# Sheet6.net
KiCad netlist of a schematic drawn in Altium Designer
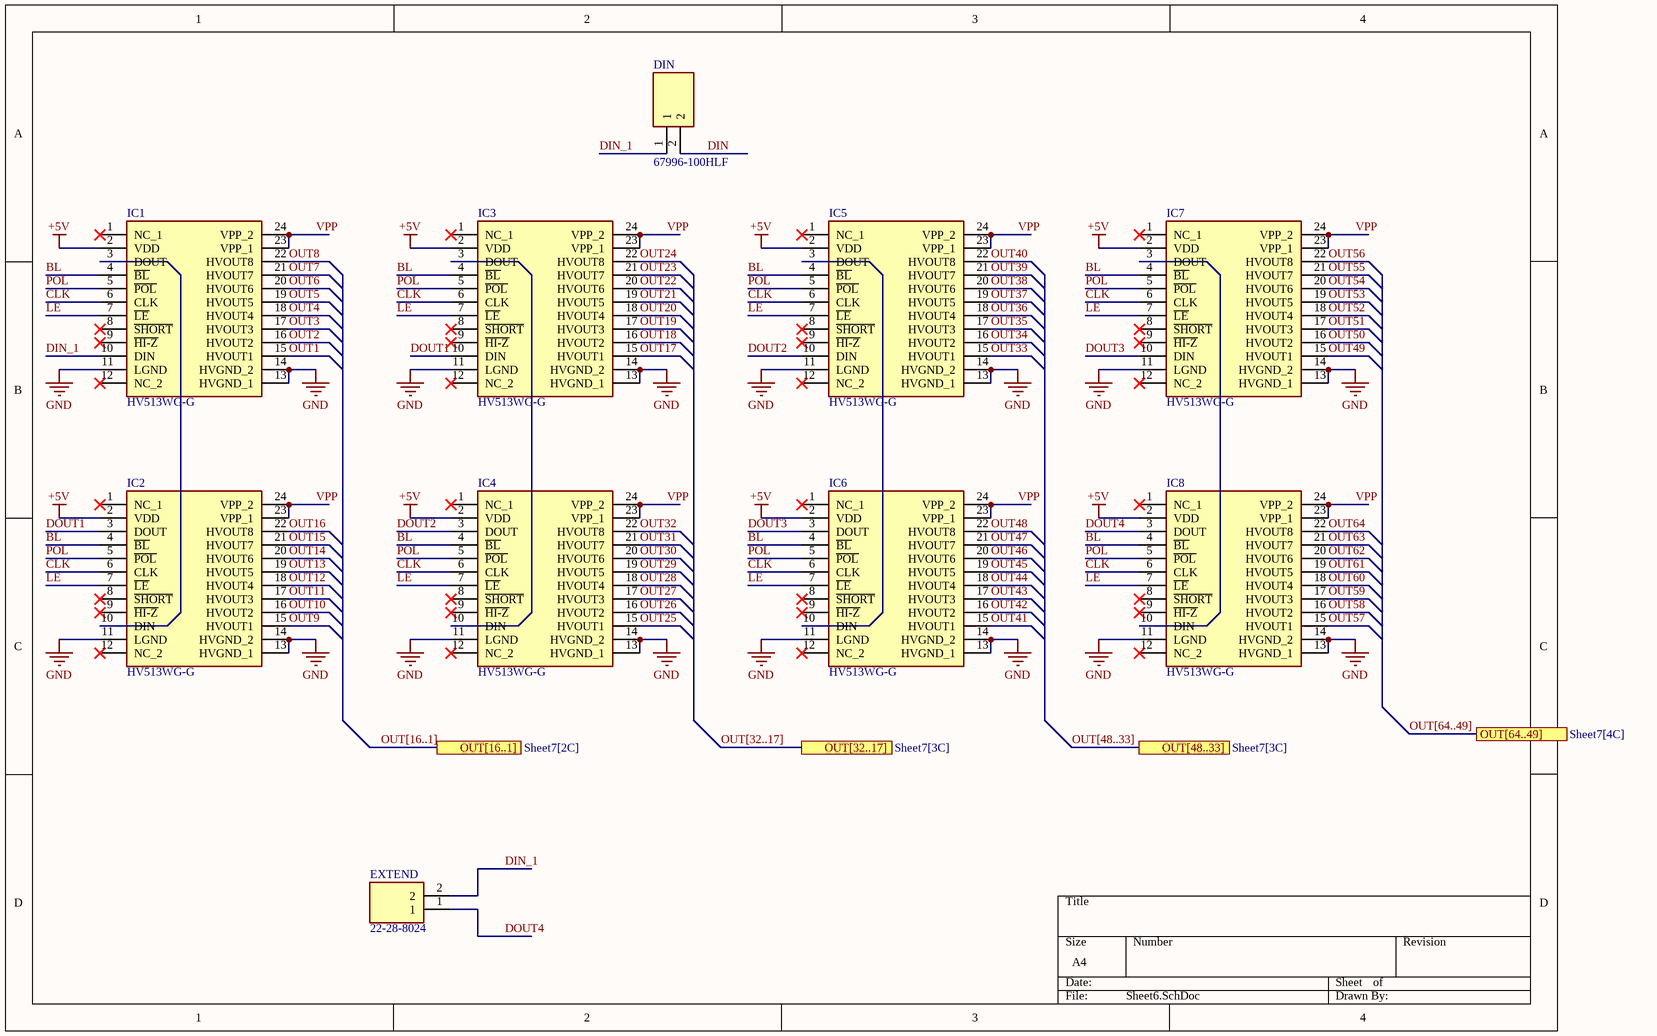
[diagram p0: Sheet6.SchDoc]

(export (version "E")
  (design (tool "Eeschema 10.0.6"))
  (components
    (comp (ref "DIN")
      (value "67996-100HLF")
      (footprint "HDRV2W67P254_2X1_254X483X858P")
      (libsource (lib "67996-100HLF") (part "67996-100HLF"))
    )
    (comp (ref "EXTEND")
      (value "22-28-8024")
      (footprint "SamacSys:HDRRA2W66P0X254_1X2_508X229X274P")
      (description "Connector")
      (libsource (lib "*") (part "22-28-8024"))
    )
    (comp (ref "IC1")
      (value "HV513WG-G")
      (footprint "SamacSys:SOIC127P1030X265-24N")
      (description "Integrated Circuit")
      (fields (field (name "MOUSER PART NUMBER") "689-HV513WG-G"))
      (libsource (lib "*") (part "HV513WG-G"))
    )
    (comp (ref "IC2")
      (value "HV513WG-G")
      (footprint "SamacSys:SOIC127P1030X265-24N")
      (description "Integrated Circuit")
      (fields (field (name "MOUSER PART NUMBER") "689-HV513WG-G"))
      (libsource (lib "*") (part "HV513WG-G"))
    )
    (comp (ref "IC3")
      (value "HV513WG-G")
      (footprint "SamacSys:SOIC127P1030X265-24N")
      (description "Integrated Circuit")
      (fields (field (name "MOUSER PART NUMBER") "689-HV513WG-G"))
      (libsource (lib "*") (part "HV513WG-G"))
    )
    (comp (ref "IC4")
      (value "HV513WG-G")
      (footprint "SamacSys:SOIC127P1030X265-24N")
      (description "Integrated Circuit")
      (fields (field (name "MOUSER PART NUMBER") "689-HV513WG-G"))
      (libsource (lib "*") (part "HV513WG-G"))
    )
    (comp (ref "IC5")
      (value "HV513WG-G")
      (footprint "SamacSys:SOIC127P1030X265-24N")
      (description "Integrated Circuit")
      (fields (field (name "MOUSER PART NUMBER") "689-HV513WG-G"))
      (libsource (lib "*") (part "HV513WG-G"))
    )
    (comp (ref "IC6")
      (value "HV513WG-G")
      (footprint "SamacSys:SOIC127P1030X265-24N")
      (description "Integrated Circuit")
      (fields (field (name "MOUSER PART NUMBER") "689-HV513WG-G"))
      (libsource (lib "*") (part "HV513WG-G"))
    )
    (comp (ref "IC7")
      (value "HV513WG-G")
      (footprint "SamacSys:SOIC127P1030X265-24N")
      (description "Integrated Circuit")
      (fields (field (name "MOUSER PART NUMBER") "689-HV513WG-G"))
      (libsource (lib "*") (part "HV513WG-G"))
    )
    (comp (ref "IC8")
      (value "HV513WG-G")
      (footprint "SamacSys:SOIC127P1030X265-24N")
      (description "Integrated Circuit")
      (fields (field (name "MOUSER PART NUMBER") "689-HV513WG-G"))
      (libsource (lib "*") (part "HV513WG-G"))
    )
  )
  (nets
    (net (code "1") (name "+5V") (class "Default")
      (node (ref "IC1") (pin "2") (pinfunction "VDD_2") (pintype "passive"))
      (node (ref "IC2") (pin "2") (pinfunction "VDD_2") (pintype "passive"))
      (node (ref "IC3") (pin "2") (pinfunction "VDD_2") (pintype "passive"))
      (node (ref "IC4") (pin "2") (pinfunction "VDD_2") (pintype "passive"))
      (node (ref "IC5") (pin "2") (pinfunction "VDD_2") (pintype "passive"))
      (node (ref "IC6") (pin "2") (pinfunction "VDD_2") (pintype "passive"))
      (node (ref "IC7") (pin "2") (pinfunction "VDD_2") (pintype "passive"))
      (node (ref "IC8") (pin "2") (pinfunction "VDD_2") (pintype "passive"))
    )
    (net (code "2") (name "/BL") (class "Default")
      (node (ref "IC1") (pin "4") (pinfunction "~{BL}_4") (pintype "passive"))
      (node (ref "IC2") (pin "4") (pinfunction "~{BL}_4") (pintype "passive"))
      (node (ref "IC3") (pin "4") (pinfunction "~{BL}_4") (pintype "passive"))
      (node (ref "IC4") (pin "4") (pinfunction "~{BL}_4") (pintype "passive"))
      (node (ref "IC5") (pin "4") (pinfunction "~{BL}_4") (pintype "passive"))
      (node (ref "IC6") (pin "4") (pinfunction "~{BL}_4") (pintype "passive"))
      (node (ref "IC7") (pin "4") (pinfunction "~{BL}_4") (pintype "passive"))
      (node (ref "IC8") (pin "4") (pinfunction "~{BL}_4") (pintype "passive"))
    )
    (net (code "3") (name "/CLK") (class "Default")
      (node (ref "IC1") (pin "6") (pinfunction "CLK_6") (pintype "passive"))
      (node (ref "IC2") (pin "6") (pinfunction "CLK_6") (pintype "passive"))
      (node (ref "IC3") (pin "6") (pinfunction "CLK_6") (pintype "passive"))
      (node (ref "IC4") (pin "6") (pinfunction "CLK_6") (pintype "passive"))
      (node (ref "IC5") (pin "6") (pinfunction "CLK_6") (pintype "passive"))
      (node (ref "IC6") (pin "6") (pinfunction "CLK_6") (pintype "passive"))
      (node (ref "IC7") (pin "6") (pinfunction "CLK_6") (pintype "passive"))
      (node (ref "IC8") (pin "6") (pinfunction "CLK_6") (pintype "passive"))
    )
    (net (code "4") (name "/DIN") (class "Default")
      (node (ref "DIN") (pin "2") (pinfunction "2_2") (pintype "passive"))
    )
    (net (code "5") (name "/DIN_1") (class "Default")
      (node (ref "DIN") (pin "1") (pinfunction "1_1") (pintype "passive"))
      (node (ref "EXTEND") (pin "2") (pinfunction "2_2") (pintype "passive"))
      (node (ref "IC1") (pin "10") (pinfunction "DIN_10") (pintype "passive"))
    )
    (net (code "6") (name "/DOUT1") (class "Default")
      (node (ref "IC2") (pin "3") (pinfunction "DOUT_3") (pintype "passive"))
      (node (ref "IC3") (pin "10") (pinfunction "DIN_10") (pintype "passive"))
    )
    (net (code "7") (name "/DOUT2") (class "Default")
      (node (ref "IC4") (pin "3") (pinfunction "DOUT_3") (pintype "passive"))
      (node (ref "IC5") (pin "10") (pinfunction "DIN_10") (pintype "passive"))
    )
    (net (code "8") (name "/DOUT3") (class "Default")
      (node (ref "IC6") (pin "3") (pinfunction "DOUT_3") (pintype "passive"))
      (node (ref "IC7") (pin "10") (pinfunction "DIN_10") (pintype "passive"))
    )
    (net (code "9") (name "/DOUT4") (class "Default")
      (node (ref "EXTEND") (pin "1") (pinfunction "1_1") (pintype "passive"))
      (node (ref "IC8") (pin "3") (pinfunction "DOUT_3") (pintype "passive"))
    )
    (net (code "10") (name "/LE") (class "Default")
      (node (ref "IC1") (pin "7") (pinfunction "~{LE}_7") (pintype "passive"))
      (node (ref "IC2") (pin "7") (pinfunction "~{LE}_7") (pintype "passive"))
      (node (ref "IC3") (pin "7") (pinfunction "~{LE}_7") (pintype "passive"))
      (node (ref "IC4") (pin "7") (pinfunction "~{LE}_7") (pintype "passive"))
      (node (ref "IC5") (pin "7") (pinfunction "~{LE}_7") (pintype "passive"))
      (node (ref "IC6") (pin "7") (pinfunction "~{LE}_7") (pintype "passive"))
      (node (ref "IC7") (pin "7") (pinfunction "~{LE}_7") (pintype "passive"))
      (node (ref "IC8") (pin "7") (pinfunction "~{LE}_7") (pintype "passive"))
    )
    (net (code "11") (name "/OUT1") (class "Default")
      (node (ref "IC1") (pin "15") (pinfunction "HVOUT1_15") (pintype "passive"))
    )
    (net (code "12") (name "/OUT2") (class "Default")
      (node (ref "IC1") (pin "16") (pinfunction "HVOUT2_16") (pintype "passive"))
    )
    (net (code "13") (name "/OUT3") (class "Default")
      (node (ref "IC1") (pin "17") (pinfunction "HVOUT3_17") (pintype "passive"))
    )
    (net (code "14") (name "/OUT4") (class "Default")
      (node (ref "IC1") (pin "18") (pinfunction "HVOUT4_18") (pintype "passive"))
    )
    (net (code "15") (name "/OUT5") (class "Default")
      (node (ref "IC1") (pin "19") (pinfunction "HVOUT5_19") (pintype "passive"))
    )
    (net (code "16") (name "/OUT6") (class "Default")
      (node (ref "IC1") (pin "20") (pinfunction "HVOUT6_20") (pintype "passive"))
    )
    (net (code "17") (name "/OUT7") (class "Default")
      (node (ref "IC1") (pin "21") (pinfunction "HVOUT7_21") (pintype "passive"))
    )
    (net (code "18") (name "/OUT8") (class "Default")
      (node (ref "IC1") (pin "22") (pinfunction "HVOUT8_22") (pintype "passive"))
    )
    (net (code "19") (name "/OUT9") (class "Default")
      (node (ref "IC2") (pin "15") (pinfunction "HVOUT1_15") (pintype "passive"))
    )
    (net (code "20") (name "/OUT10") (class "Default")
      (node (ref "IC2") (pin "16") (pinfunction "HVOUT2_16") (pintype "passive"))
    )
    (net (code "21") (name "/OUT11") (class "Default")
      (node (ref "IC2") (pin "17") (pinfunction "HVOUT3_17") (pintype "passive"))
    )
    (net (code "22") (name "/OUT12") (class "Default")
      (node (ref "IC2") (pin "18") (pinfunction "HVOUT4_18") (pintype "passive"))
    )
    (net (code "23") (name "/OUT13") (class "Default")
      (node (ref "IC2") (pin "19") (pinfunction "HVOUT5_19") (pintype "passive"))
    )
    (net (code "24") (name "/OUT14") (class "Default")
      (node (ref "IC2") (pin "20") (pinfunction "HVOUT6_20") (pintype "passive"))
    )
    (net (code "25") (name "/OUT15") (class "Default")
      (node (ref "IC2") (pin "21") (pinfunction "HVOUT7_21") (pintype "passive"))
    )
    (net (code "26") (name "/OUT16") (class "Default")
      (node (ref "IC2") (pin "22") (pinfunction "HVOUT8_22") (pintype "passive"))
    )
    (net (code "27") (name "/OUT17") (class "Default")
      (node (ref "IC3") (pin "15") (pinfunction "HVOUT1_15") (pintype "passive"))
    )
    (net (code "28") (name "/OUT18") (class "Default")
      (node (ref "IC3") (pin "16") (pinfunction "HVOUT2_16") (pintype "passive"))
    )
    (net (code "29") (name "/OUT19") (class "Default")
      (node (ref "IC3") (pin "17") (pinfunction "HVOUT3_17") (pintype "passive"))
    )
    (net (code "30") (name "/OUT20") (class "Default")
      (node (ref "IC3") (pin "18") (pinfunction "HVOUT4_18") (pintype "passive"))
    )
    (net (code "31") (name "/OUT21") (class "Default")
      (node (ref "IC3") (pin "19") (pinfunction "HVOUT5_19") (pintype "passive"))
    )
    (net (code "32") (name "/OUT22") (class "Default")
      (node (ref "IC3") (pin "20") (pinfunction "HVOUT6_20") (pintype "passive"))
    )
    (net (code "33") (name "/OUT23") (class "Default")
      (node (ref "IC3") (pin "21") (pinfunction "HVOUT7_21") (pintype "passive"))
    )
    (net (code "34") (name "/OUT24") (class "Default")
      (node (ref "IC3") (pin "22") (pinfunction "HVOUT8_22") (pintype "passive"))
    )
    (net (code "35") (name "/OUT25") (class "Default")
      (node (ref "IC4") (pin "15") (pinfunction "HVOUT1_15") (pintype "passive"))
    )
    (net (code "36") (name "/OUT26") (class "Default")
      (node (ref "IC4") (pin "16") (pinfunction "HVOUT2_16") (pintype "passive"))
    )
    (net (code "37") (name "/OUT27") (class "Default")
      (node (ref "IC4") (pin "17") (pinfunction "HVOUT3_17") (pintype "passive"))
    )
    (net (code "38") (name "/OUT28") (class "Default")
      (node (ref "IC4") (pin "18") (pinfunction "HVOUT4_18") (pintype "passive"))
    )
    (net (code "39") (name "/OUT29") (class "Default")
      (node (ref "IC4") (pin "19") (pinfunction "HVOUT5_19") (pintype "passive"))
    )
    (net (code "40") (name "/OUT30") (class "Default")
      (node (ref "IC4") (pin "20") (pinfunction "HVOUT6_20") (pintype "passive"))
    )
    (net (code "41") (name "/OUT31") (class "Default")
      (node (ref "IC4") (pin "21") (pinfunction "HVOUT7_21") (pintype "passive"))
    )
    (net (code "42") (name "/OUT32") (class "Default")
      (node (ref "IC4") (pin "22") (pinfunction "HVOUT8_22") (pintype "passive"))
    )
    (net (code "43") (name "/OUT33") (class "Default")
      (node (ref "IC5") (pin "15") (pinfunction "HVOUT1_15") (pintype "passive"))
    )
    (net (code "44") (name "/OUT34") (class "Default")
      (node (ref "IC5") (pin "16") (pinfunction "HVOUT2_16") (pintype "passive"))
    )
    (net (code "45") (name "/OUT35") (class "Default")
      (node (ref "IC5") (pin "17") (pinfunction "HVOUT3_17") (pintype "passive"))
    )
    (net (code "46") (name "/OUT36") (class "Default")
      (node (ref "IC5") (pin "18") (pinfunction "HVOUT4_18") (pintype "passive"))
    )
    (net (code "47") (name "/OUT37") (class "Default")
      (node (ref "IC5") (pin "19") (pinfunction "HVOUT5_19") (pintype "passive"))
    )
    (net (code "48") (name "/OUT38") (class "Default")
      (node (ref "IC5") (pin "20") (pinfunction "HVOUT6_20") (pintype "passive"))
    )
    (net (code "49") (name "/OUT39") (class "Default")
      (node (ref "IC5") (pin "21") (pinfunction "HVOUT7_21") (pintype "passive"))
    )
    (net (code "50") (name "/OUT40") (class "Default")
      (node (ref "IC5") (pin "22") (pinfunction "HVOUT8_22") (pintype "passive"))
    )
    (net (code "51") (name "/OUT41") (class "Default")
      (node (ref "IC6") (pin "15") (pinfunction "HVOUT1_15") (pintype "passive"))
    )
    (net (code "52") (name "/OUT42") (class "Default")
      (node (ref "IC6") (pin "16") (pinfunction "HVOUT2_16") (pintype "passive"))
    )
    (net (code "53") (name "/OUT43") (class "Default")
      (node (ref "IC6") (pin "17") (pinfunction "HVOUT3_17") (pintype "passive"))
    )
    (net (code "54") (name "/OUT44") (class "Default")
      (node (ref "IC6") (pin "18") (pinfunction "HVOUT4_18") (pintype "passive"))
    )
    (net (code "55") (name "/OUT45") (class "Default")
      (node (ref "IC6") (pin "19") (pinfunction "HVOUT5_19") (pintype "passive"))
    )
    (net (code "56") (name "/OUT46") (class "Default")
      (node (ref "IC6") (pin "20") (pinfunction "HVOUT6_20") (pintype "passive"))
    )
    (net (code "57") (name "/OUT47") (class "Default")
      (node (ref "IC6") (pin "21") (pinfunction "HVOUT7_21") (pintype "passive"))
    )
    (net (code "58") (name "/OUT48") (class "Default")
      (node (ref "IC6") (pin "22") (pinfunction "HVOUT8_22") (pintype "passive"))
    )
    (net (code "59") (name "/OUT49") (class "Default")
      (node (ref "IC7") (pin "15") (pinfunction "HVOUT1_15") (pintype "passive"))
    )
    (net (code "60") (name "/OUT50") (class "Default")
      (node (ref "IC7") (pin "16") (pinfunction "HVOUT2_16") (pintype "passive"))
    )
    (net (code "61") (name "/OUT51") (class "Default")
      (node (ref "IC7") (pin "17") (pinfunction "HVOUT3_17") (pintype "passive"))
    )
    (net (code "62") (name "/OUT52") (class "Default")
      (node (ref "IC7") (pin "18") (pinfunction "HVOUT4_18") (pintype "passive"))
    )
    (net (code "63") (name "/OUT53") (class "Default")
      (node (ref "IC7") (pin "19") (pinfunction "HVOUT5_19") (pintype "passive"))
    )
    (net (code "64") (name "/OUT54") (class "Default")
      (node (ref "IC7") (pin "20") (pinfunction "HVOUT6_20") (pintype "passive"))
    )
    (net (code "65") (name "/OUT55") (class "Default")
      (node (ref "IC7") (pin "21") (pinfunction "HVOUT7_21") (pintype "passive"))
    )
    (net (code "66") (name "/OUT56") (class "Default")
      (node (ref "IC7") (pin "22") (pinfunction "HVOUT8_22") (pintype "passive"))
    )
    (net (code "67") (name "/OUT57") (class "Default")
      (node (ref "IC8") (pin "15") (pinfunction "HVOUT1_15") (pintype "passive"))
    )
    (net (code "68") (name "/OUT58") (class "Default")
      (node (ref "IC8") (pin "16") (pinfunction "HVOUT2_16") (pintype "passive"))
    )
    (net (code "69") (name "/OUT59") (class "Default")
      (node (ref "IC8") (pin "17") (pinfunction "HVOUT3_17") (pintype "passive"))
    )
    (net (code "70") (name "/OUT60") (class "Default")
      (node (ref "IC8") (pin "18") (pinfunction "HVOUT4_18") (pintype "passive"))
    )
    (net (code "71") (name "/OUT61") (class "Default")
      (node (ref "IC8") (pin "19") (pinfunction "HVOUT5_19") (pintype "passive"))
    )
    (net (code "72") (name "/OUT62") (class "Default")
      (node (ref "IC8") (pin "20") (pinfunction "HVOUT6_20") (pintype "passive"))
    )
    (net (code "73") (name "/OUT63") (class "Default")
      (node (ref "IC8") (pin "21") (pinfunction "HVOUT7_21") (pintype "passive"))
    )
    (net (code "74") (name "/OUT64") (class "Default")
      (node (ref "IC8") (pin "22") (pinfunction "HVOUT8_22") (pintype "passive"))
    )
    (net (code "79") (name "/POL") (class "Default")
      (node (ref "IC1") (pin "5") (pinfunction "~{POL}_5") (pintype "passive"))
      (node (ref "IC2") (pin "5") (pinfunction "~{POL}_5") (pintype "passive"))
      (node (ref "IC3") (pin "5") (pinfunction "~{POL}_5") (pintype "passive"))
      (node (ref "IC4") (pin "5") (pinfunction "~{POL}_5") (pintype "passive"))
      (node (ref "IC5") (pin "5") (pinfunction "~{POL}_5") (pintype "passive"))
      (node (ref "IC6") (pin "5") (pinfunction "~{POL}_5") (pintype "passive"))
      (node (ref "IC7") (pin "5") (pinfunction "~{POL}_5") (pintype "passive"))
      (node (ref "IC8") (pin "5") (pinfunction "~{POL}_5") (pintype "passive"))
    )
    (net (code "80") (name "/VPP") (class "Default")
      (node (ref "IC1") (pin "23") (pinfunction "VPP_1_23") (pintype "passive"))
      (node (ref "IC1") (pin "24") (pinfunction "VPP_2_24") (pintype "passive"))
      (node (ref "IC2") (pin "23") (pinfunction "VPP_1_23") (pintype "passive"))
      (node (ref "IC2") (pin "24") (pinfunction "VPP_2_24") (pintype "passive"))
      (node (ref "IC3") (pin "23") (pinfunction "VPP_1_23") (pintype "passive"))
      (node (ref "IC3") (pin "24") (pinfunction "VPP_2_24") (pintype "passive"))
      (node (ref "IC4") (pin "23") (pinfunction "VPP_1_23") (pintype "passive"))
      (node (ref "IC4") (pin "24") (pinfunction "VPP_2_24") (pintype "passive"))
      (node (ref "IC5") (pin "23") (pinfunction "VPP_1_23") (pintype "passive"))
      (node (ref "IC5") (pin "24") (pinfunction "VPP_2_24") (pintype "passive"))
      (node (ref "IC6") (pin "23") (pinfunction "VPP_1_23") (pintype "passive"))
      (node (ref "IC6") (pin "24") (pinfunction "VPP_2_24") (pintype "passive"))
      (node (ref "IC7") (pin "23") (pinfunction "VPP_1_23") (pintype "passive"))
      (node (ref "IC7") (pin "24") (pinfunction "VPP_2_24") (pintype "passive"))
      (node (ref "IC8") (pin "23") (pinfunction "VPP_1_23") (pintype "passive"))
      (node (ref "IC8") (pin "24") (pinfunction "VPP_2_24") (pintype "passive"))
    )
    (net (code "81") (name "GND") (class "Default")
      (node (ref "IC1") (pin "11") (pinfunction "LGND_11") (pintype "passive"))
      (node (ref "IC1") (pin "13") (pinfunction "HVGND_1_13") (pintype "passive"))
      (node (ref "IC1") (pin "14") (pinfunction "HVGND_2_14") (pintype "passive"))
      (node (ref "IC2") (pin "11") (pinfunction "LGND_11") (pintype "passive"))
      (node (ref "IC2") (pin "13") (pinfunction "HVGND_1_13") (pintype "passive"))
      (node (ref "IC2") (pin "14") (pinfunction "HVGND_2_14") (pintype "passive"))
      (node (ref "IC3") (pin "11") (pinfunction "LGND_11") (pintype "passive"))
      (node (ref "IC3") (pin "13") (pinfunction "HVGND_1_13") (pintype "passive"))
      (node (ref "IC3") (pin "14") (pinfunction "HVGND_2_14") (pintype "passive"))
      (node (ref "IC4") (pin "11") (pinfunction "LGND_11") (pintype "passive"))
      (node (ref "IC4") (pin "13") (pinfunction "HVGND_1_13") (pintype "passive"))
      (node (ref "IC4") (pin "14") (pinfunction "HVGND_2_14") (pintype "passive"))
      (node (ref "IC5") (pin "11") (pinfunction "LGND_11") (pintype "passive"))
      (node (ref "IC5") (pin "13") (pinfunction "HVGND_1_13") (pintype "passive"))
      (node (ref "IC5") (pin "14") (pinfunction "HVGND_2_14") (pintype "passive"))
      (node (ref "IC6") (pin "11") (pinfunction "LGND_11") (pintype "passive"))
      (node (ref "IC6") (pin "13") (pinfunction "HVGND_1_13") (pintype "passive"))
      (node (ref "IC6") (pin "14") (pinfunction "HVGND_2_14") (pintype "passive"))
      (node (ref "IC7") (pin "11") (pinfunction "LGND_11") (pintype "passive"))
      (node (ref "IC7") (pin "13") (pinfunction "HVGND_1_13") (pintype "passive"))
      (node (ref "IC7") (pin "14") (pinfunction "HVGND_2_14") (pintype "passive"))
      (node (ref "IC8") (pin "11") (pinfunction "LGND_11") (pintype "passive"))
      (node (ref "IC8") (pin "13") (pinfunction "HVGND_1_13") (pintype "passive"))
      (node (ref "IC8") (pin "14") (pinfunction "HVGND_2_14") (pintype "passive"))
    )
    (net (code "82") (name "Net-(IC1-DOUT)") (class "Default")
      (node (ref "IC1") (pin "3") (pinfunction "DOUT_3") (pintype "passive"))
      (node (ref "IC2") (pin "10") (pinfunction "DIN_10") (pintype "passive"))
    )
    (net (code "83") (name "Net-(IC3-DOUT)") (class "Default")
      (node (ref "IC3") (pin "3") (pinfunction "DOUT_3") (pintype "passive"))
      (node (ref "IC4") (pin "10") (pinfunction "DIN_10") (pintype "passive"))
    )
    (net (code "84") (name "Net-(IC5-DOUT)") (class "Default")
      (node (ref "IC5") (pin "3") (pinfunction "DOUT_3") (pintype "passive"))
      (node (ref "IC6") (pin "10") (pinfunction "DIN_10") (pintype "passive"))
    )
    (net (code "85") (name "Net-(IC7-DOUT)") (class "Default")
      (node (ref "IC7") (pin "3") (pinfunction "DOUT_3") (pintype "passive"))
      (node (ref "IC8") (pin "10") (pinfunction "DIN_10") (pintype "passive"))
    )
    (net (code "86") (name "unconnected-(IC1-NC_1-Pad1)") (class "Default")
      (node (ref "IC1") (pin "1") (pinfunction "NC_1_1") (pintype "passive+no_connect"))
    )
    (net (code "87") (name "unconnected-(IC1-NC_2-Pad12)") (class "Default")
      (node (ref "IC1") (pin "12") (pinfunction "NC_2_12") (pintype "passive+no_connect"))
    )
    (net (code "88") (name "unconnected-(IC1-~{HI-Z}-Pad9)") (class "Default")
      (node (ref "IC1") (pin "9") (pinfunction "~{HI-Z}_9") (pintype "passive+no_connect"))
    )
    (net (code "89") (name "unconnected-(IC1-~{SHORT}-Pad8)") (class "Default")
      (node (ref "IC1") (pin "8") (pinfunction "~{SHORT}_8") (pintype "passive+no_connect"))
    )
    (net (code "90") (name "unconnected-(IC2-NC_1-Pad1)") (class "Default")
      (node (ref "IC2") (pin "1") (pinfunction "NC_1_1") (pintype "passive+no_connect"))
    )
    (net (code "91") (name "unconnected-(IC2-NC_2-Pad12)") (class "Default")
      (node (ref "IC2") (pin "12") (pinfunction "NC_2_12") (pintype "passive+no_connect"))
    )
    (net (code "92") (name "unconnected-(IC2-~{HI-Z}-Pad9)") (class "Default")
      (node (ref "IC2") (pin "9") (pinfunction "~{HI-Z}_9") (pintype "passive+no_connect"))
    )
    (net (code "93") (name "unconnected-(IC2-~{SHORT}-Pad8)") (class "Default")
      (node (ref "IC2") (pin "8") (pinfunction "~{SHORT}_8") (pintype "passive+no_connect"))
    )
    (net (code "94") (name "unconnected-(IC3-NC_1-Pad1)") (class "Default")
      (node (ref "IC3") (pin "1") (pinfunction "NC_1_1") (pintype "passive+no_connect"))
    )
    (net (code "95") (name "unconnected-(IC3-NC_2-Pad12)") (class "Default")
      (node (ref "IC3") (pin "12") (pinfunction "NC_2_12") (pintype "passive+no_connect"))
    )
    (net (code "96") (name "unconnected-(IC3-~{HI-Z}-Pad9)") (class "Default")
      (node (ref "IC3") (pin "9") (pinfunction "~{HI-Z}_9") (pintype "passive+no_connect"))
    )
    (net (code "97") (name "unconnected-(IC3-~{SHORT}-Pad8)") (class "Default")
      (node (ref "IC3") (pin "8") (pinfunction "~{SHORT}_8") (pintype "passive+no_connect"))
    )
    (net (code "98") (name "unconnected-(IC4-NC_1-Pad1)") (class "Default")
      (node (ref "IC4") (pin "1") (pinfunction "NC_1_1") (pintype "passive+no_connect"))
    )
    (net (code "99") (name "unconnected-(IC4-NC_2-Pad12)") (class "Default")
      (node (ref "IC4") (pin "12") (pinfunction "NC_2_12") (pintype "passive+no_connect"))
    )
    (net (code "100") (name "unconnected-(IC4-~{HI-Z}-Pad9)") (class "Default")
      (node (ref "IC4") (pin "9") (pinfunction "~{HI-Z}_9") (pintype "passive+no_connect"))
    )
    (net (code "101") (name "unconnected-(IC4-~{SHORT}-Pad8)") (class "Default")
      (node (ref "IC4") (pin "8") (pinfunction "~{SHORT}_8") (pintype "passive+no_connect"))
    )
    (net (code "102") (name "unconnected-(IC5-NC_1-Pad1)") (class "Default")
      (node (ref "IC5") (pin "1") (pinfunction "NC_1_1") (pintype "passive+no_connect"))
    )
    (net (code "103") (name "unconnected-(IC5-NC_2-Pad12)") (class "Default")
      (node (ref "IC5") (pin "12") (pinfunction "NC_2_12") (pintype "passive+no_connect"))
    )
    (net (code "104") (name "unconnected-(IC5-~{HI-Z}-Pad9)") (class "Default")
      (node (ref "IC5") (pin "9") (pinfunction "~{HI-Z}_9") (pintype "passive+no_connect"))
    )
    (net (code "105") (name "unconnected-(IC5-~{SHORT}-Pad8)") (class "Default")
      (node (ref "IC5") (pin "8") (pinfunction "~{SHORT}_8") (pintype "passive+no_connect"))
    )
    (net (code "106") (name "unconnected-(IC6-NC_1-Pad1)") (class "Default")
      (node (ref "IC6") (pin "1") (pinfunction "NC_1_1") (pintype "passive+no_connect"))
    )
    (net (code "107") (name "unconnected-(IC6-NC_2-Pad12)") (class "Default")
      (node (ref "IC6") (pin "12") (pinfunction "NC_2_12") (pintype "passive+no_connect"))
    )
    (net (code "108") (name "unconnected-(IC6-~{HI-Z}-Pad9)") (class "Default")
      (node (ref "IC6") (pin "9") (pinfunction "~{HI-Z}_9") (pintype "passive+no_connect"))
    )
    (net (code "109") (name "unconnected-(IC6-~{SHORT}-Pad8)") (class "Default")
      (node (ref "IC6") (pin "8") (pinfunction "~{SHORT}_8") (pintype "passive+no_connect"))
    )
    (net (code "110") (name "unconnected-(IC7-NC_1-Pad1)") (class "Default")
      (node (ref "IC7") (pin "1") (pinfunction "NC_1_1") (pintype "passive+no_connect"))
    )
    (net (code "111") (name "unconnected-(IC7-NC_2-Pad12)") (class "Default")
      (node (ref "IC7") (pin "12") (pinfunction "NC_2_12") (pintype "passive+no_connect"))
    )
    (net (code "112") (name "unconnected-(IC7-~{HI-Z}-Pad9)") (class "Default")
      (node (ref "IC7") (pin "9") (pinfunction "~{HI-Z}_9") (pintype "passive+no_connect"))
    )
    (net (code "113") (name "unconnected-(IC7-~{SHORT}-Pad8)") (class "Default")
      (node (ref "IC7") (pin "8") (pinfunction "~{SHORT}_8") (pintype "passive+no_connect"))
    )
    (net (code "114") (name "unconnected-(IC8-NC_1-Pad1)") (class "Default")
      (node (ref "IC8") (pin "1") (pinfunction "NC_1_1") (pintype "passive+no_connect"))
    )
    (net (code "115") (name "unconnected-(IC8-NC_2-Pad12)") (class "Default")
      (node (ref "IC8") (pin "12") (pinfunction "NC_2_12") (pintype "passive+no_connect"))
    )
    (net (code "116") (name "unconnected-(IC8-~{HI-Z}-Pad9)") (class "Default")
      (node (ref "IC8") (pin "9") (pinfunction "~{HI-Z}_9") (pintype "passive+no_connect"))
    )
    (net (code "117") (name "unconnected-(IC8-~{SHORT}-Pad8)") (class "Default")
      (node (ref "IC8") (pin "8") (pinfunction "~{SHORT}_8") (pintype "passive+no_connect"))
    )
  )
)
